# Arduino-Mega-Shield-EAGLE.net
KiCad netlist of a schematic drawn in EAGLE
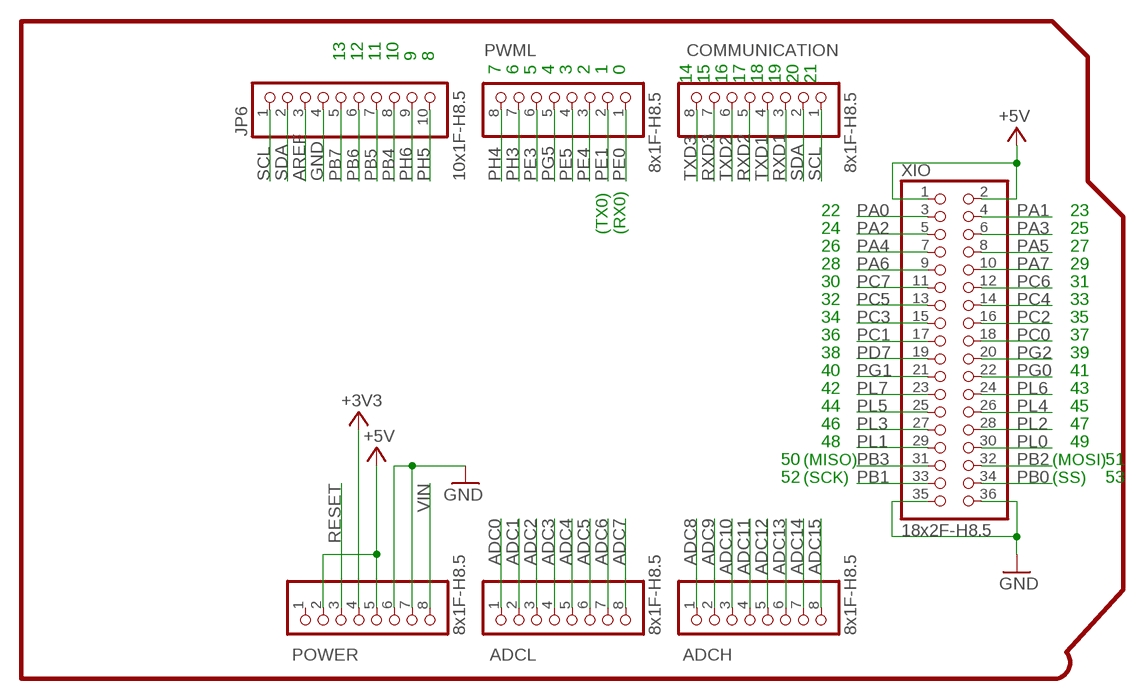
[diagram p0: schematic, sheet 1]

(export (version "E")
  (design (tool "Eeschema 10.0.6"))
  (components
    (comp (ref "ADCH")
      (value "8x1F-H8.5")
      (footprint "eagle-import:1X08")
      (libsource (lib "eagle-import") (part "PINHD-1X8"))
    )
    (comp (ref "ADCL")
      (value "8x1F-H8.5")
      (footprint "eagle-import:1X08")
      (libsource (lib "eagle-import") (part "PINHD-1X8"))
    )
    (comp (ref "COMMUNICATION")
      (value "8x1F-H8.5")
      (footprint "eagle-import:1X08")
      (libsource (lib "eagle-import") (part "PINHD-1X8"))
    )
    (comp (ref "JP6")
      (value "10x1F-H8.5")
      (footprint "eagle-import:1X10")
      (libsource (lib "eagle-import") (part "PINHD-1X10_ARD"))
    )
    (comp (ref "POWER")
      (value "8x1F-H8.5")
      (footprint "eagle-import:1X08")
      (libsource (lib "eagle-import") (part "PINHD-1X8"))
    )
    (comp (ref "PWML")
      (value "8x1F-H8.5")
      (footprint "eagle-import:1X08")
      (libsource (lib "eagle-import") (part "PINHD-1X8"))
    )
    (comp (ref "XIO")
      (value "18x2F-H8.5")
      (footprint "eagle-import:2X18")
      (libsource (lib "eagle-import") (part "PINHD-2X18"))
    )
  )
  (nets
    (net (code "1") (name "+3V3") (class "Default")
      (node (ref "POWER") (pin "4") (pinfunction "4_4") (pintype "passive"))
    )
    (net (code "2") (name "+5V") (class "Default")
      (node (ref "POWER") (pin "2") (pinfunction "2_2") (pintype "passive"))
      (node (ref "POWER") (pin "5") (pinfunction "5_5") (pintype "passive"))
      (node (ref "XIO") (pin "1") (pinfunction "1_1") (pintype "passive"))
      (node (ref "XIO") (pin "2") (pinfunction "2_2") (pintype "passive"))
    )
    (net (code "3") (name "/ADC0") (class "Default")
      (node (ref "ADCL") (pin "1") (pinfunction "1_1") (pintype "passive"))
    )
    (net (code "4") (name "/ADC1") (class "Default")
      (node (ref "ADCL") (pin "2") (pinfunction "2_2") (pintype "passive"))
    )
    (net (code "5") (name "/ADC2") (class "Default")
      (node (ref "ADCL") (pin "3") (pinfunction "3_3") (pintype "passive"))
    )
    (net (code "6") (name "/ADC3") (class "Default")
      (node (ref "ADCL") (pin "4") (pinfunction "4_4") (pintype "passive"))
    )
    (net (code "7") (name "/ADC4") (class "Default")
      (node (ref "ADCL") (pin "5") (pinfunction "5_5") (pintype "passive"))
    )
    (net (code "8") (name "/ADC5") (class "Default")
      (node (ref "ADCL") (pin "6") (pinfunction "6_6") (pintype "passive"))
    )
    (net (code "9") (name "/ADC6") (class "Default")
      (node (ref "ADCL") (pin "7") (pinfunction "7_7") (pintype "passive"))
    )
    (net (code "10") (name "/ADC7") (class "Default")
      (node (ref "ADCL") (pin "8") (pinfunction "8_8") (pintype "passive"))
    )
    (net (code "11") (name "/ADC8") (class "Default")
      (node (ref "ADCH") (pin "1") (pinfunction "1_1") (pintype "passive"))
    )
    (net (code "12") (name "/ADC9") (class "Default")
      (node (ref "ADCH") (pin "2") (pinfunction "2_2") (pintype "passive"))
    )
    (net (code "13") (name "/ADC10") (class "Default")
      (node (ref "ADCH") (pin "3") (pinfunction "3_3") (pintype "passive"))
    )
    (net (code "14") (name "/ADC11") (class "Default")
      (node (ref "ADCH") (pin "4") (pinfunction "4_4") (pintype "passive"))
    )
    (net (code "15") (name "/ADC12") (class "Default")
      (node (ref "ADCH") (pin "5") (pinfunction "5_5") (pintype "passive"))
    )
    (net (code "16") (name "/ADC13") (class "Default")
      (node (ref "ADCH") (pin "6") (pinfunction "6_6") (pintype "passive"))
    )
    (net (code "17") (name "/ADC14") (class "Default")
      (node (ref "ADCH") (pin "7") (pinfunction "7_7") (pintype "passive"))
    )
    (net (code "18") (name "/ADC15") (class "Default")
      (node (ref "ADCH") (pin "8") (pinfunction "8_8") (pintype "passive"))
    )
    (net (code "19") (name "/AREF") (class "Default")
      (node (ref "JP6") (pin "3") (pinfunction "3_3") (pintype "passive"))
    )
    (net (code "20") (name "/PA0") (class "Default")
      (node (ref "XIO") (pin "3") (pinfunction "3_3") (pintype "passive"))
    )
    (net (code "21") (name "/PA1") (class "Default")
      (node (ref "XIO") (pin "4") (pinfunction "4_4") (pintype "passive"))
    )
    (net (code "22") (name "/PA2") (class "Default")
      (node (ref "XIO") (pin "5") (pinfunction "5_5") (pintype "passive"))
    )
    (net (code "23") (name "/PA3") (class "Default")
      (node (ref "XIO") (pin "6") (pinfunction "6_6") (pintype "passive"))
    )
    (net (code "24") (name "/PA4") (class "Default")
      (node (ref "XIO") (pin "7") (pinfunction "7_7") (pintype "passive"))
    )
    (net (code "25") (name "/PA5") (class "Default")
      (node (ref "XIO") (pin "8") (pinfunction "8_8") (pintype "passive"))
    )
    (net (code "26") (name "/PA6") (class "Default")
      (node (ref "XIO") (pin "9") (pinfunction "9_9") (pintype "passive"))
    )
    (net (code "27") (name "/PA7") (class "Default")
      (node (ref "XIO") (pin "10") (pinfunction "10_10") (pintype "passive"))
    )
    (net (code "28") (name "/PB0") (class "Default")
      (node (ref "XIO") (pin "34") (pinfunction "34_34") (pintype "passive"))
    )
    (net (code "29") (name "/PB1") (class "Default")
      (node (ref "XIO") (pin "33") (pinfunction "33_33") (pintype "passive"))
    )
    (net (code "30") (name "/PB2") (class "Default")
      (node (ref "XIO") (pin "32") (pinfunction "32_32") (pintype "passive"))
    )
    (net (code "31") (name "/PB3") (class "Default")
      (node (ref "XIO") (pin "31") (pinfunction "31_31") (pintype "passive"))
    )
    (net (code "32") (name "/PB4") (class "Default")
      (node (ref "JP6") (pin "8") (pinfunction "8_8") (pintype "passive"))
    )
    (net (code "33") (name "/PB5") (class "Default")
      (node (ref "JP6") (pin "7") (pinfunction "7_7") (pintype "passive"))
    )
    (net (code "34") (name "/PB6") (class "Default")
      (node (ref "JP6") (pin "6") (pinfunction "6_6") (pintype "passive"))
    )
    (net (code "35") (name "/PB7") (class "Default")
      (node (ref "JP6") (pin "5") (pinfunction "5_5") (pintype "passive"))
    )
    (net (code "36") (name "/PC0") (class "Default")
      (node (ref "XIO") (pin "18") (pinfunction "18_18") (pintype "passive"))
    )
    (net (code "37") (name "/PC1") (class "Default")
      (node (ref "XIO") (pin "17") (pinfunction "17_17") (pintype "passive"))
    )
    (net (code "38") (name "/PC2") (class "Default")
      (node (ref "XIO") (pin "16") (pinfunction "16_16") (pintype "passive"))
    )
    (net (code "39") (name "/PC3") (class "Default")
      (node (ref "XIO") (pin "15") (pinfunction "15_15") (pintype "passive"))
    )
    (net (code "40") (name "/PC4") (class "Default")
      (node (ref "XIO") (pin "14") (pinfunction "14_14") (pintype "passive"))
    )
    (net (code "41") (name "/PC5") (class "Default")
      (node (ref "XIO") (pin "13") (pinfunction "13_13") (pintype "passive"))
    )
    (net (code "42") (name "/PC6") (class "Default")
      (node (ref "XIO") (pin "12") (pinfunction "12_12") (pintype "passive"))
    )
    (net (code "43") (name "/PC7") (class "Default")
      (node (ref "XIO") (pin "11") (pinfunction "11_11") (pintype "passive"))
    )
    (net (code "44") (name "/PD7") (class "Default")
      (node (ref "XIO") (pin "19") (pinfunction "19_19") (pintype "passive"))
    )
    (net (code "45") (name "/PE0") (class "Default")
      (node (ref "PWML") (pin "1") (pinfunction "1_1") (pintype "passive"))
    )
    (net (code "46") (name "/PE1") (class "Default")
      (node (ref "PWML") (pin "2") (pinfunction "2_2") (pintype "passive"))
    )
    (net (code "47") (name "/PE3") (class "Default")
      (node (ref "PWML") (pin "6") (pinfunction "6_6") (pintype "passive"))
    )
    (net (code "48") (name "/PE4") (class "Default")
      (node (ref "PWML") (pin "3") (pinfunction "3_3") (pintype "passive"))
    )
    (net (code "49") (name "/PE5") (class "Default")
      (node (ref "PWML") (pin "4") (pinfunction "4_4") (pintype "passive"))
    )
    (net (code "50") (name "/PG0") (class "Default")
      (node (ref "XIO") (pin "22") (pinfunction "22_22") (pintype "passive"))
    )
    (net (code "51") (name "/PG1") (class "Default")
      (node (ref "XIO") (pin "21") (pinfunction "21_21") (pintype "passive"))
    )
    (net (code "52") (name "/PG2") (class "Default")
      (node (ref "XIO") (pin "20") (pinfunction "20_20") (pintype "passive"))
    )
    (net (code "53") (name "/PG5") (class "Default")
      (node (ref "PWML") (pin "5") (pinfunction "5_5") (pintype "passive"))
    )
    (net (code "54") (name "/PH3") (class "Default")
      (node (ref "PWML") (pin "7") (pinfunction "7_7") (pintype "passive"))
    )
    (net (code "55") (name "/PH4") (class "Default")
      (node (ref "PWML") (pin "8") (pinfunction "8_8") (pintype "passive"))
    )
    (net (code "56") (name "/PH5") (class "Default")
      (node (ref "JP6") (pin "10") (pinfunction "10_10") (pintype "passive"))
    )
    (net (code "57") (name "/PH6") (class "Default")
      (node (ref "JP6") (pin "9") (pinfunction "9_9") (pintype "passive"))
    )
    (net (code "58") (name "/PL0") (class "Default")
      (node (ref "XIO") (pin "30") (pinfunction "30_30") (pintype "passive"))
    )
    (net (code "59") (name "/PL1") (class "Default")
      (node (ref "XIO") (pin "29") (pinfunction "29_29") (pintype "passive"))
    )
    (net (code "60") (name "/PL2") (class "Default")
      (node (ref "XIO") (pin "28") (pinfunction "28_28") (pintype "passive"))
    )
    (net (code "61") (name "/PL3") (class "Default")
      (node (ref "XIO") (pin "27") (pinfunction "27_27") (pintype "passive"))
    )
    (net (code "62") (name "/PL4") (class "Default")
      (node (ref "XIO") (pin "26") (pinfunction "26_26") (pintype "passive"))
    )
    (net (code "63") (name "/PL5") (class "Default")
      (node (ref "XIO") (pin "25") (pinfunction "25_25") (pintype "passive"))
    )
    (net (code "64") (name "/PL6") (class "Default")
      (node (ref "XIO") (pin "24") (pinfunction "24_24") (pintype "passive"))
    )
    (net (code "65") (name "/PL7") (class "Default")
      (node (ref "XIO") (pin "23") (pinfunction "23_23") (pintype "passive"))
    )
    (net (code "66") (name "/RESET") (class "Default")
      (node (ref "POWER") (pin "3") (pinfunction "3_3") (pintype "passive"))
    )
    (net (code "67") (name "/RXD1") (class "Default")
      (node (ref "COMMUNICATION") (pin "3") (pinfunction "3_3") (pintype "passive"))
    )
    (net (code "68") (name "/RXD2") (class "Default")
      (node (ref "COMMUNICATION") (pin "5") (pinfunction "5_5") (pintype "passive"))
    )
    (net (code "69") (name "/RXD3") (class "Default")
      (node (ref "COMMUNICATION") (pin "7") (pinfunction "7_7") (pintype "passive"))
    )
    (net (code "70") (name "/SCL") (class "Default")
      (node (ref "COMMUNICATION") (pin "1") (pinfunction "1_1") (pintype "passive"))
      (node (ref "JP6") (pin "1") (pinfunction "1_1") (pintype "passive"))
    )
    (net (code "71") (name "/SDA") (class "Default")
      (node (ref "COMMUNICATION") (pin "2") (pinfunction "2_2") (pintype "passive"))
      (node (ref "JP6") (pin "2") (pinfunction "2_2") (pintype "passive"))
    )
    (net (code "72") (name "/TXD1") (class "Default")
      (node (ref "COMMUNICATION") (pin "4") (pinfunction "4_4") (pintype "passive"))
    )
    (net (code "73") (name "/TXD2") (class "Default")
      (node (ref "COMMUNICATION") (pin "6") (pinfunction "6_6") (pintype "passive"))
    )
    (net (code "74") (name "/TXD3") (class "Default")
      (node (ref "COMMUNICATION") (pin "8") (pinfunction "8_8") (pintype "passive"))
    )
    (net (code "75") (name "/VIN") (class "Default")
      (node (ref "POWER") (pin "8") (pinfunction "8_8") (pintype "passive"))
    )
    (net (code "76") (name "GND") (class "Default")
      (node (ref "JP6") (pin "4") (pinfunction "4_4") (pintype "passive"))
      (node (ref "POWER") (pin "6") (pinfunction "6_6") (pintype "passive"))
      (node (ref "POWER") (pin "7") (pinfunction "7_7") (pintype "passive"))
      (node (ref "XIO") (pin "35") (pinfunction "35_35") (pintype "passive"))
      (node (ref "XIO") (pin "36") (pinfunction "36_36") (pintype "passive"))
    )
    (net (code "77") (name "unconnected-(POWER-Pad1)") (class "Default")
      (node (ref "POWER") (pin "1") (pinfunction "1_1") (pintype "passive"))
    )
  )
)
